# current_mp6519.net
KiCad netlist of a schematic drawn in Altium Designer
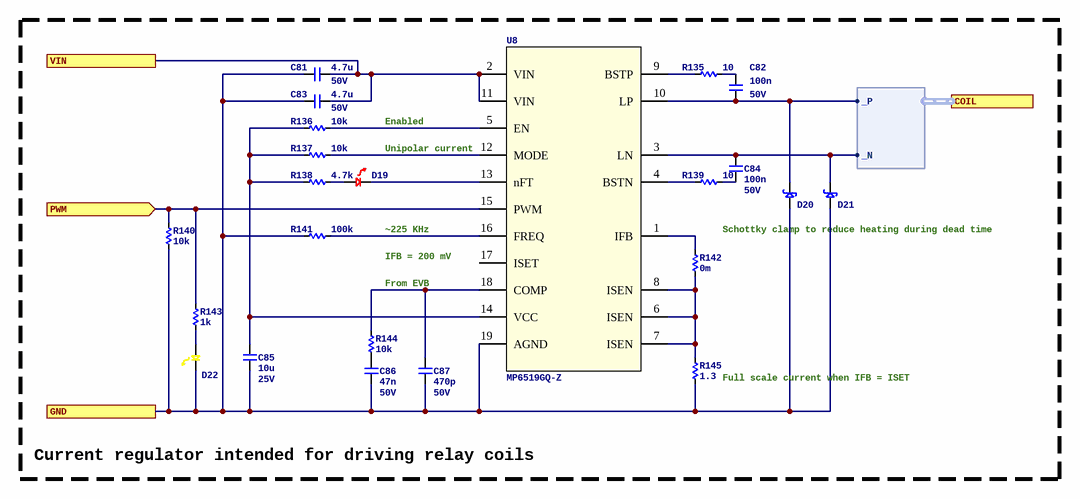
[diagram p0: current_mp6519.SchDoc]

(export (version "E")
  (design (tool "Eeschema 10.0.6"))
  (components
    (comp (ref "C81")
      (value "0805B475K500NT")
      (footprint "C0805")
      (fields
        (field (name "CAPACITANCE") "4.7u")
        (field (name "MANUFACTURER") "FH (Guangdong Fenghua Advanced Tech)")
        (field (name "VOLTAGE RATING") "50V")
      )
      (libsource (lib "database") (part "__template_cap"))
    )
    (comp (ref "C82")
      (value "CL05B104KB54PNC")
      (footprint "C0402")
      (fields
        (field (name "CAPACITANCE") "100n")
        (field (name "MANUFACTURER") "Samsung Electro-Mechanics")
        (field (name "VOLTAGE RATING") "50V")
      )
      (libsource (lib "database") (part "__template_cap"))
    )
    (comp (ref "C83")
      (value "0805B475K500NT")
      (footprint "C0805")
      (fields
        (field (name "CAPACITANCE") "4.7u")
        (field (name "MANUFACTURER") "FH (Guangdong Fenghua Advanced Tech)")
        (field (name "VOLTAGE RATING") "50V")
      )
      (libsource (lib "database") (part "__template_cap"))
    )
    (comp (ref "C84")
      (value "CL05B104KB54PNC")
      (footprint "C0402")
      (fields
        (field (name "CAPACITANCE") "100n")
        (field (name "MANUFACTURER") "Samsung Electro-Mechanics")
        (field (name "VOLTAGE RATING") "50V")
      )
      (libsource (lib "database") (part "__template_cap"))
    )
    (comp (ref "C85")
      (value "CL10A106MA8NRNC")
      (footprint "C0603")
      (fields
        (field (name "CAPACITANCE") "10u")
        (field (name "MANUFACTURER") "Samsung Electro-Mechanics")
        (field (name "VOLTAGE RATING") "25V")
      )
      (libsource (lib "database") (part "__template_cap"))
    )
    (comp (ref "C86")
      (value "0402B473K500NT")
      (footprint "C0402")
      (fields
        (field (name "CAPACITANCE") "47n")
        (field (name "MANUFACTURER") "FH(Guangdong Fenghua Advanced Tech)")
        (field (name "VOLTAGE RATING") "50V")
      )
      (libsource (lib "database") (part "__template_cap"))
    )
    (comp (ref "C87")
      (value "GRM1555C1H471JA01D")
      (footprint "C0402")
      (fields
        (field (name "CAPACITANCE") "470p")
        (field (name "MANUFACTURER") "Murata Electronics")
        (field (name "VOLTAGE RATING") "50V")
      )
      (libsource (lib "database") (part "__template_cap"))
    )
    (comp (ref "D19")
      (value "LTST-C190KRKT")
      (footprint "LED_0603P_RED")
      (description "LED SUPER RED CLEAR 0603 SMD")
      (fields (field (name "MANUFACTURER") "Lite-On Inc"))
      (libsource (lib "SSCP") (part "LED_0603_RED_LTST-C190KRKT"))
    )
    (comp (ref "D20")
      (value "MSS2P2-M3/89A")
      (footprint "ESMP")
      (description "DIODE SCHOTTKY 20V 2A MICROSMP")
      (fields (field (name "MANUFACTURER") "Vishay Semiconductor Diodes Division"))
      (libsource (lib "SSCP") (part "SCHOTTKY_MSS2P2-M3/89A"))
    )
    (comp (ref "D21")
      (value "MSS2P2-M3/89A")
      (footprint "ESMP")
      (description "DIODE SCHOTTKY 20V 2A MICROSMP")
      (fields (field (name "MANUFACTURER") "Vishay Semiconductor Diodes Division"))
      (libsource (lib "SSCP") (part "SCHOTTKY_MSS2P2-M3/89A"))
    )
    (comp (ref "D22")
      (value "LTST-C190YKT")
      (footprint "LED_0603P_YELLOW")
      (description "LED YELLOW CLEAR 0603 SMD")
      (fields (field (name "MANUFACTURER") "Lite-On Inc"))
      (libsource (lib "SSCP") (part "LED_0603_YELLOW_LTST-C190YKT"))
    )
    (comp (ref "R135")
      (value "10")
      (footprint "R0402")
      (fields
        (field (name "TOLERANCE") "1%")
        (field (name "MANUFACTURER PART NUMBER") "FRC0402F10R0TS")
        (field (name "MANUFACTURER") "FOJAN")
      )
      (libsource (lib "database") (part "__template_resistor"))
    )
    (comp (ref "R136")
      (value "10k")
      (footprint "R0402")
      (fields
        (field (name "TOLERANCE") "1%")
        (field (name "MANUFACTURER PART NUMBER") "0402WGF1002TCE")
        (field (name "MANUFACTURER") "UNI-ROYAL(Uniroyal Elec)")
      )
      (libsource (lib "database") (part "__template_resistor"))
    )
    (comp (ref "R137")
      (value "10k")
      (footprint "R0402")
      (fields
        (field (name "TOLERANCE") "1%")
        (field (name "MANUFACTURER PART NUMBER") "0402WGF1002TCE")
        (field (name "MANUFACTURER") "UNI-ROYAL(Uniroyal Elec)")
      )
      (libsource (lib "database") (part "__template_resistor"))
    )
    (comp (ref "R138")
      (value "4.7k")
      (footprint "R0402")
      (fields
        (field (name "TOLERANCE") "1%")
        (field (name "MANUFACTURER PART NUMBER") "0402WGF4701TCE")
        (field (name "MANUFACTURER") "UNI-ROYAL(Uniroyal Elec)")
      )
      (libsource (lib "database") (part "__template_resistor"))
    )
    (comp (ref "R139")
      (value "10")
      (footprint "R0402")
      (fields
        (field (name "TOLERANCE") "1%")
        (field (name "MANUFACTURER PART NUMBER") "FRC0402F10R0TS")
        (field (name "MANUFACTURER") "FOJAN")
      )
      (libsource (lib "database") (part "__template_resistor"))
    )
    (comp (ref "R140")
      (value "10k")
      (footprint "R0402")
      (fields
        (field (name "TOLERANCE") "1%")
        (field (name "MANUFACTURER PART NUMBER") "0402WGF1002TCE")
        (field (name "MANUFACTURER") "UNI-ROYAL(Uniroyal Elec)")
      )
      (libsource (lib "database") (part "__template_resistor"))
    )
    (comp (ref "R141")
      (value "100k")
      (footprint "R0402")
      (fields
        (field (name "TOLERANCE") "1%")
        (field (name "MANUFACTURER PART NUMBER") "0402WGF1003TCE")
        (field (name "MANUFACTURER") "UNI-ROYAL(Uniroyal Elec)")
      )
      (libsource (lib "database") (part "__template_resistor"))
    )
    (comp (ref "R142")
      (value "0m")
      (footprint "R0402")
      (fields
        (field (name "MANUFACTURER PART NUMBER") "0402WGF0000TCE")
        (field (name "MANUFACTURER") "UNI-ROYAL(Uniroyal Elec)")
      )
      (libsource (lib "database") (part "__template_resistor"))
    )
    (comp (ref "R143")
      (value "1k")
      (footprint "R0402")
      (fields
        (field (name "TOLERANCE") "1%")
        (field (name "MANUFACTURER PART NUMBER") "0402WGF1001TCE")
        (field (name "MANUFACTURER") "UNI-ROYAL(Uniroyal Elec)")
      )
      (libsource (lib "database") (part "__template_resistor"))
    )
    (comp (ref "R144")
      (value "10k")
      (footprint "R0402")
      (fields
        (field (name "TOLERANCE") "1%")
        (field (name "MANUFACTURER PART NUMBER") "0402WGF1002TCE")
        (field (name "MANUFACTURER") "UNI-ROYAL(Uniroyal Elec)")
      )
      (libsource (lib "database") (part "__template_resistor"))
    )
    (comp (ref "R145")
      (value "1.3")
      (footprint "R1206")
      (fields
        (field (name "TOLERANCE") "1%")
        (field (name "MANUFACTURER PART NUMBER") "HP06W2F130KT5E")
        (field (name "MANUFACTURER") "UNI-ROYAL(Uniroyal Elec)")
      )
      (libsource (lib "database") (part "__template_resistor"))
    )
    (comp (ref "U8")
      (value "MP6519GQ-Z")
      (footprint "MP6519")
      (description "2.5V - 28V, 5A, H-bridge Current Regulator")
      (fields (field (name "MANUFACTURER") "Monolithic Power Systems"))
      (libsource (lib "SSCP") (part "CURRENT_BRIDGE_MP6519GQ-Z"))
    )
  )
  (nets
    (net (code "2") (name "/GND") (class "Default")
      (node (ref "C81") (pin "1") (pintype "passive"))
      (node (ref "C83") (pin "1") (pintype "passive"))
      (node (ref "C85") (pin "2") (pintype "passive"))
      (node (ref "C86") (pin "2") (pintype "passive"))
      (node (ref "C87") (pin "2") (pintype "passive"))
      (node (ref "D20") (pin "2") (pintype "passive"))
      (node (ref "D21") (pin "2") (pintype "passive"))
      (node (ref "D22") (pin "1") (pintype "passive"))
      (node (ref "R140") (pin "1") (pintype "passive"))
      (node (ref "R141") (pin "2") (pintype "passive"))
      (node (ref "R145") (pin "1") (pintype "passive"))
      (node (ref "U8") (pin "19") (pinfunction "AGND_19") (pintype "passive"))
    )
    (net (code "3") (name "/PWM") (class "Default")
      (node (ref "R140") (pin "2") (pintype "passive"))
      (node (ref "R143") (pin "1") (pintype "passive"))
      (node (ref "U8") (pin "15") (pinfunction "PWM_15") (pintype "passive"))
    )
    (net (code "4") (name "/VIN") (class "Default")
      (node (ref "C81") (pin "2") (pintype "passive"))
      (node (ref "C83") (pin "2") (pintype "passive"))
      (node (ref "U8") (pin "11") (pinfunction "VIN_11") (pintype "passive"))
      (node (ref "U8") (pin "2") (pinfunction "VIN_2") (pintype "passive"))
    )
    (net (code "6") (name "Net-(C82-Pad1)") (class "Default")
      (node (ref "C82") (pin "1") (pintype "passive"))
      (node (ref "R135") (pin "2") (pintype "passive"))
    )
    (net (code "7") (name "Net-(C84-Pad2)") (class "Default")
      (node (ref "C84") (pin "2") (pintype "passive"))
      (node (ref "R139") (pin "2") (pintype "passive"))
    )
    (net (code "8") (name "Net-(C86-Pad1)") (class "Default")
      (node (ref "C86") (pin "1") (pintype "passive"))
      (node (ref "R144") (pin "1") (pintype "passive"))
    )
    (net (code "9") (name "Net-(D19-Pad2)") (class "Default")
      (node (ref "D19") (pin "2") (pintype "passive"))
      (node (ref "R138") (pin "2") (pintype "passive"))
    )
    (net (code "10") (name "Net-(D22-Pad2)") (class "Default")
      (node (ref "D22") (pin "2") (pintype "passive"))
      (node (ref "R143") (pin "2") (pintype "passive"))
    )
    (net (code "11") (name "Net-(R142-Pad1)") (class "Default")
      (node (ref "R142") (pin "1") (pintype "passive"))
      (node (ref "R145") (pin "2") (pintype "passive"))
      (node (ref "U8") (pin "6") (pinfunction "ISEN_6") (pintype "passive"))
      (node (ref "U8") (pin "7") (pinfunction "ISEN_7") (pintype "passive"))
      (node (ref "U8") (pin "8") (pinfunction "ISEN_8") (pintype "passive"))
    )
    (net (code "12") (name "Net-(U8-BSTN)") (class "Default")
      (node (ref "R139") (pin "1") (pintype "passive"))
      (node (ref "U8") (pin "4") (pinfunction "BSTN_4") (pintype "passive"))
    )
    (net (code "13") (name "Net-(U8-BSTP)") (class "Default")
      (node (ref "R135") (pin "1") (pintype "passive"))
      (node (ref "U8") (pin "9") (pinfunction "BSTP_9") (pintype "passive"))
    )
    (net (code "14") (name "Net-(U8-COMP)") (class "Default")
      (node (ref "C87") (pin "1") (pintype "passive"))
      (node (ref "R144") (pin "2") (pintype "passive"))
      (node (ref "U8") (pin "18") (pinfunction "COMP_18") (pintype "passive"))
    )
    (net (code "15") (name "Net-(U8-EN)") (class "Default")
      (node (ref "R136") (pin "2") (pintype "passive"))
      (node (ref "U8") (pin "5") (pinfunction "EN_5") (pintype "passive"))
    )
    (net (code "16") (name "Net-(U8-FREQ)") (class "Default")
      (node (ref "R141") (pin "1") (pintype "passive"))
      (node (ref "U8") (pin "16") (pinfunction "FREQ_16") (pintype "passive"))
    )
    (net (code "17") (name "Net-(U8-IFB)") (class "Default")
      (node (ref "R142") (pin "2") (pintype "passive"))
      (node (ref "U8") (pin "1") (pinfunction "IFB_1") (pintype "passive"))
    )
    (net (code "18") (name "Net-(U8-LN)") (class "Default")
      (node (ref "C84") (pin "1") (pintype "passive"))
      (node (ref "D21") (pin "1") (pintype "passive"))
      (node (ref "U8") (pin "3") (pinfunction "LN_3") (pintype "passive"))
    )
    (net (code "19") (name "Net-(U8-LP)") (class "Default")
      (node (ref "C82") (pin "2") (pintype "passive"))
      (node (ref "D20") (pin "1") (pintype "passive"))
      (node (ref "U8") (pin "10") (pinfunction "LP_10") (pintype "passive"))
    )
    (net (code "20") (name "Net-(U8-MODE)") (class "Default")
      (node (ref "R137") (pin "2") (pintype "passive"))
      (node (ref "U8") (pin "12") (pinfunction "MODE_12") (pintype "passive"))
    )
    (net (code "21") (name "Net-(U8-VCC)") (class "Default")
      (node (ref "C85") (pin "1") (pintype "passive"))
      (node (ref "R136") (pin "1") (pintype "passive"))
      (node (ref "R137") (pin "1") (pintype "passive"))
      (node (ref "R138") (pin "1") (pintype "passive"))
      (node (ref "U8") (pin "14") (pinfunction "VCC_14") (pintype "passive"))
    )
    (net (code "22") (name "Net-(U8-nFT)") (class "Default")
      (node (ref "D19") (pin "1") (pintype "passive"))
      (node (ref "U8") (pin "13") (pinfunction "nFT_13") (pintype "passive"))
    )
    (net (code "23") (name "unconnected-(U8-ISET-Pad17)") (class "Default")
      (node (ref "U8") (pin "17") (pinfunction "ISET_17") (pintype "passive"))
    )
  )
)
